# HD3SS460-PORT2.net
KiCad netlist of a schematic drawn in Altium Designer
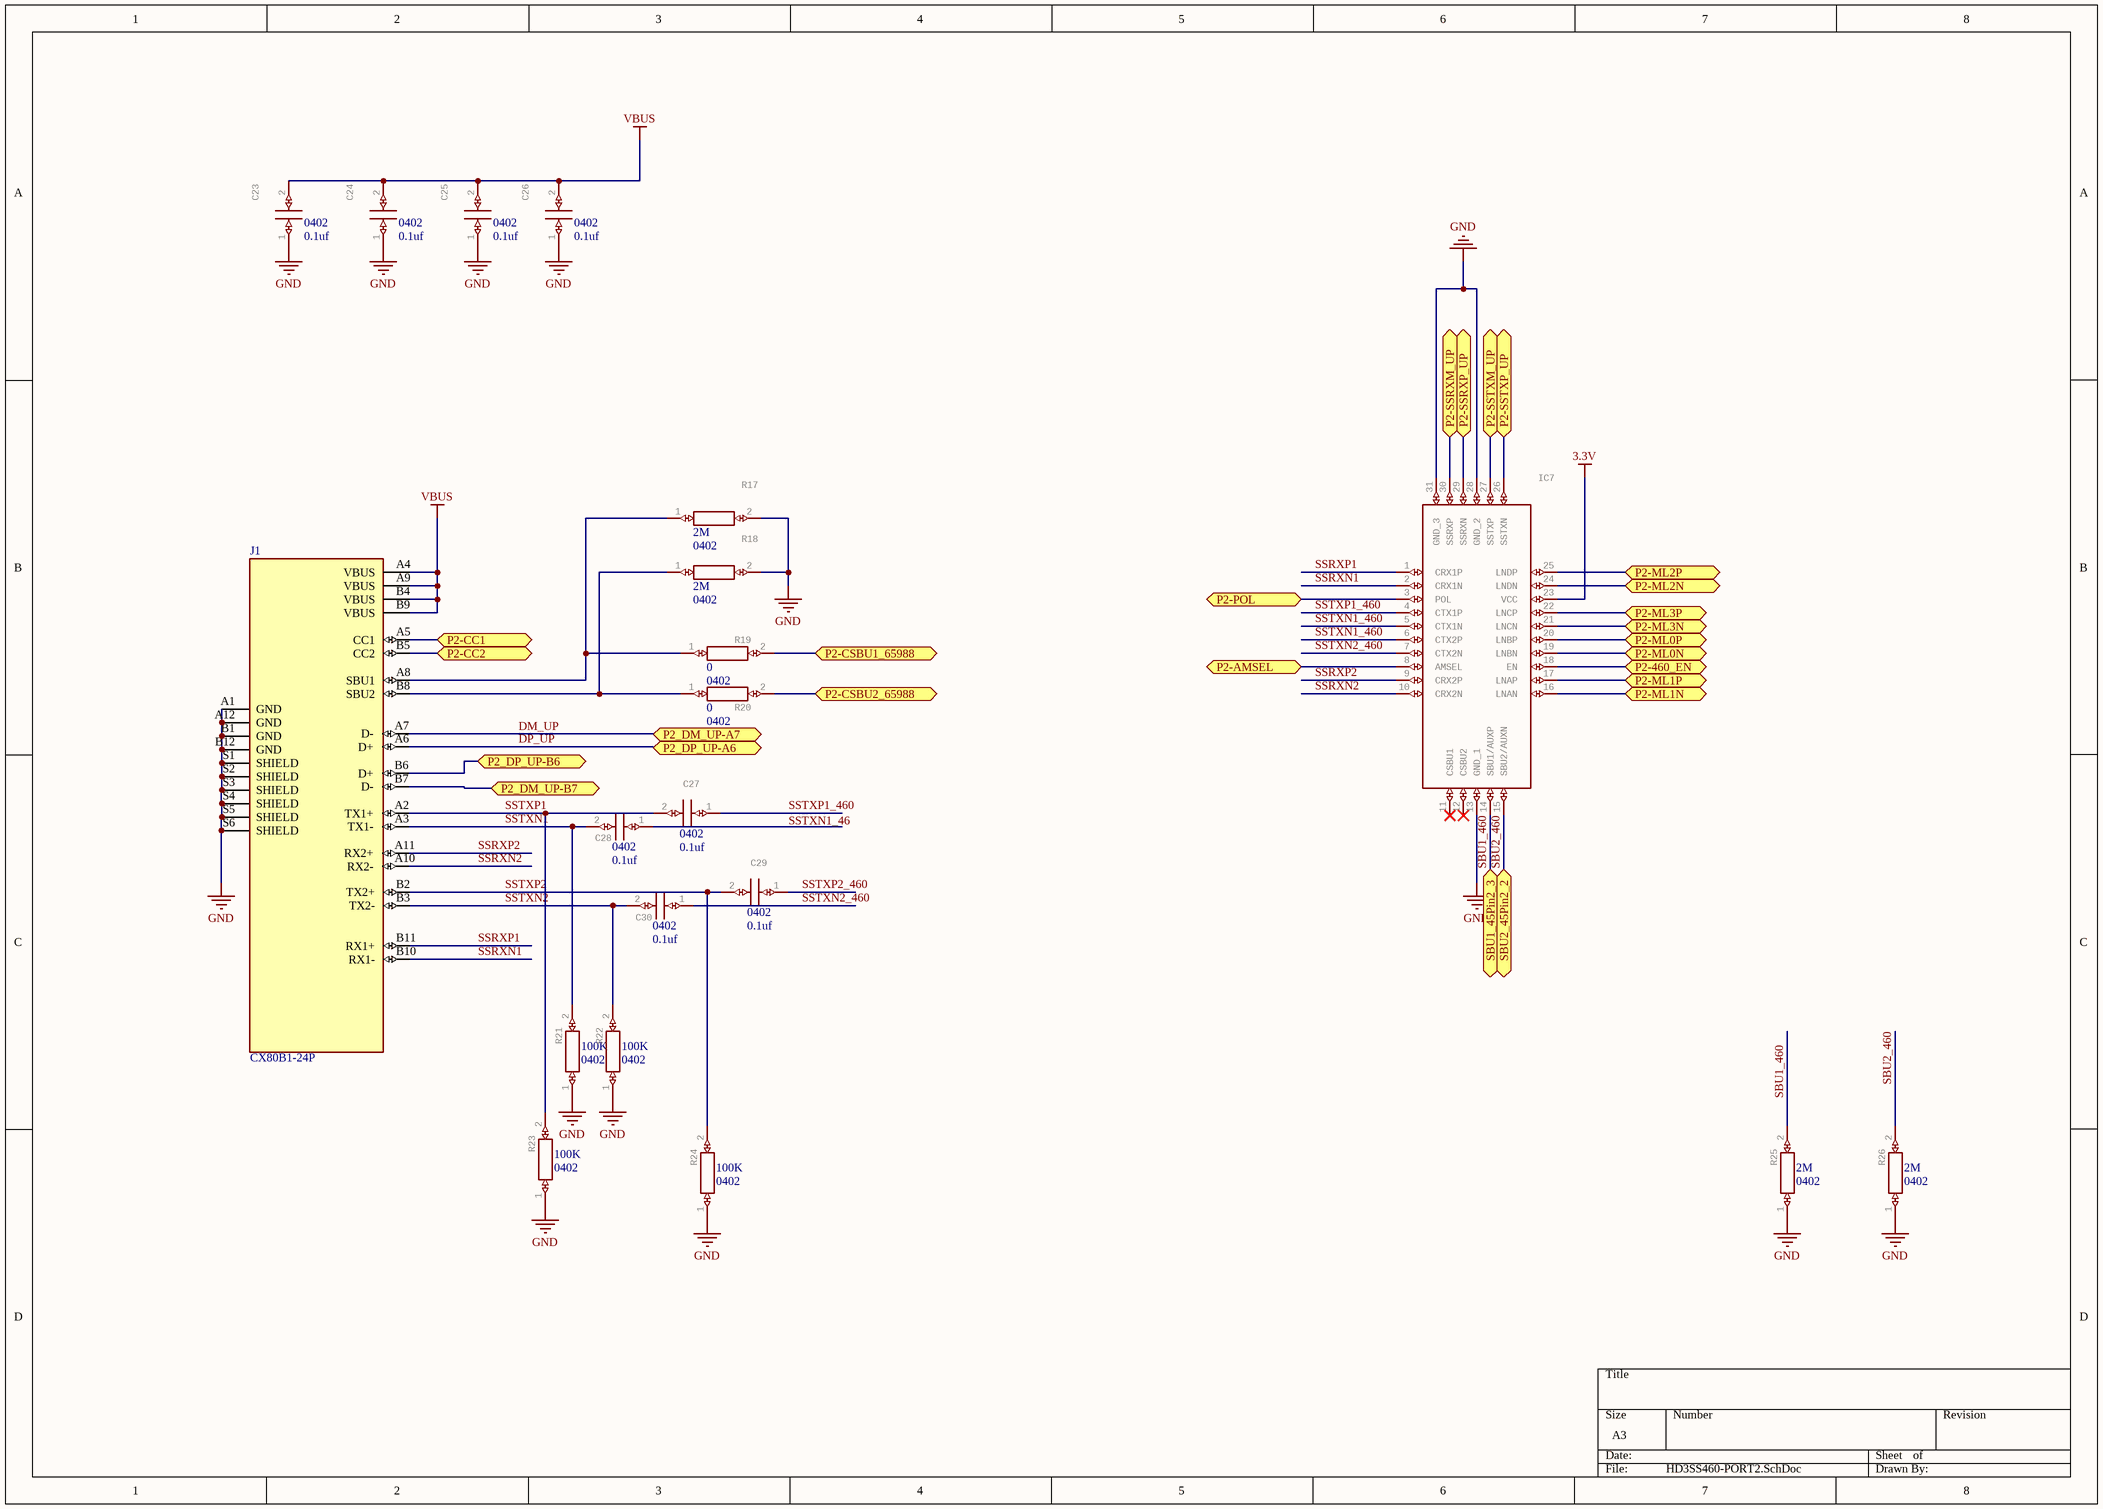
[diagram p0: HD3SS460-PORT2.SchDoc]

(export (version "E")
  (design (tool "Eeschema 10.0.6"))
  (components
    (comp (ref "C23")
      (value "0.1uf")
      (footprint "CAPC1005X56N")
      (fields
        (field (name "MANUFACTURER_PART_NUMBER") "04025C104KAT2A")
        (field (name "MOUSER_PART_NUMBER") "581-04025C104KAT2A")
        (field (name "PACKAGE") "0402")
        (field (name "Comment") "Multilayer Ceramic Capacitors MLCC - SMD/SMT 50V .1uF X7R 0402 10% Tol   Source:  Datasheet")
      )
      (libsource (lib "C0402-GP") (part "04025C104KAT2A"))
    )
    (comp (ref "C24")
      (value "0.1uf")
      (footprint "CAPC1005X56N")
      (fields
        (field (name "MANUFACTURER_PART_NUMBER") "04025C104KAT2A")
        (field (name "MOUSER_PART_NUMBER") "581-04025C104KAT2A")
        (field (name "PACKAGE") "0402")
        (field (name "Comment") "Multilayer Ceramic Capacitors MLCC - SMD/SMT 50V .1uF X7R 0402 10% Tol   Source:  Datasheet")
      )
      (libsource (lib "C0402-GP") (part "04025C104KAT2A"))
    )
    (comp (ref "C25")
      (value "0.1uf")
      (footprint "CAPC1005X56N")
      (fields
        (field (name "MANUFACTURER_PART_NUMBER") "04025C104KAT2A")
        (field (name "MOUSER_PART_NUMBER") "581-04025C104KAT2A")
        (field (name "PACKAGE") "0402")
        (field (name "Comment") "Multilayer Ceramic Capacitors MLCC - SMD/SMT 50V .1uF X7R 0402 10% Tol   Source:  Datasheet")
      )
      (libsource (lib "C0402-GP") (part "04025C104KAT2A"))
    )
    (comp (ref "C26")
      (value "0.1uf")
      (footprint "CAPC1005X56N")
      (fields
        (field (name "MANUFACTURER_PART_NUMBER") "04025C104KAT2A")
        (field (name "MOUSER_PART_NUMBER") "581-04025C104KAT2A")
        (field (name "PACKAGE") "0402")
        (field (name "Comment") "Multilayer Ceramic Capacitors MLCC - SMD/SMT 50V .1uF X7R 0402 10% Tol   Source:  Datasheet")
      )
      (libsource (lib "C0402-GP") (part "04025C104KAT2A"))
    )
    (comp (ref "C27")
      (value "0.1uf")
      (footprint "CAPC1005X56N")
      (fields
        (field (name "MANUFACTURER_PART_NUMBER") "04025C104KAT2A")
        (field (name "MOUSER_PART_NUMBER") "581-04025C104KAT2A")
        (field (name "PACKAGE") "0402")
        (field (name "Comment") "Multilayer Ceramic Capacitors MLCC - SMD/SMT 50V .1uF X7R 0402 10% Tol   Source:  Datasheet")
      )
      (libsource (lib "C0402-GP") (part "04025C104KAT2A"))
    )
    (comp (ref "C28")
      (value "0.1uf")
      (footprint "CAPC1005X56N")
      (fields
        (field (name "MANUFACTURER_PART_NUMBER") "04025C104KAT2A")
        (field (name "MOUSER_PART_NUMBER") "581-04025C104KAT2A")
        (field (name "PACKAGE") "0402")
        (field (name "Comment") "Multilayer Ceramic Capacitors MLCC - SMD/SMT 50V .1uF X7R 0402 10% Tol   Source:  Datasheet")
      )
      (libsource (lib "C0402-GP") (part "04025C104KAT2A"))
    )
    (comp (ref "C29")
      (value "0.1uf")
      (footprint "CAPC1005X56N")
      (fields
        (field (name "MANUFACTURER_PART_NUMBER") "04025C104KAT2A")
        (field (name "MOUSER_PART_NUMBER") "581-04025C104KAT2A")
        (field (name "PACKAGE") "0402")
        (field (name "Comment") "Multilayer Ceramic Capacitors MLCC - SMD/SMT 50V .1uF X7R 0402 10% Tol   Source:  Datasheet")
      )
      (libsource (lib "C0402-GP") (part "04025C104KAT2A"))
    )
    (comp (ref "C30")
      (value "0.1uf")
      (footprint "CAPC1005X56N")
      (fields
        (field (name "MANUFACTURER_PART_NUMBER") "04025C104KAT2A")
        (field (name "MOUSER_PART_NUMBER") "581-04025C104KAT2A")
        (field (name "PACKAGE") "0402")
        (field (name "Comment") "Multilayer Ceramic Capacitors MLCC - SMD/SMT 50V .1uF X7R 0402 10% Tol   Source:  Datasheet")
      )
      (libsource (lib "C0402-GP") (part "04025C104KAT2A"))
    )
    (comp (ref "IC7")
      (value "USB Type-C Alternate Mode 4x6 Differential Switch   Source:  Datasheet")
      (footprint "QFN40P250X450X80-31N")
      (fields
        (field (name "MANUFACTURER_PART_NUMBER") "HD3SS460RNHR")
        (field (name "MOUSER_PART_NUMBER") "595-HD3SS460RNHR")
      )
      (libsource (lib "HD3SS460RNHR") (part "HD3SS460RNHR"))
    )
    (comp (ref "J1")
      (value "CX80B1-24P")
      (footprint "HIROSE_CX80B1-24P")
      (fields
        (field (name "DIGI-KEY_PART_NUMBER") "26-CX80B1-24PCT-ND")
        (field (name "MF") "Hirose Electric Co Ltd")
      )
      (libsource (lib "CX80B1-24P") (part "CX80B1-24P"))
    )
    (comp (ref "R17")
      (value "2M")
      (footprint "RESC1005X40N")
      (fields
        (field (name "MANUFACTURER_PART_NUMBER") "RC0402FR-071KL")
        (field (name "MOUSER_PART_NUMBER") "603-RC0402FR-071KL")
        (field (name "PACKAGE") "0402")
        (field (name "Comment") "GENERAL PURPOSE CHIP RESISTORS   Source:  Datasheet")
      )
      (libsource (lib "R0402-GP") (part "RC0402FR-071KL"))
    )
    (comp (ref "R18")
      (value "2M")
      (footprint "RESC1005X40N")
      (fields
        (field (name "MANUFACTURER_PART_NUMBER") "RC0402FR-071KL")
        (field (name "MOUSER_PART_NUMBER") "603-RC0402FR-071KL")
        (field (name "PACKAGE") "0402")
        (field (name "Comment") "GENERAL PURPOSE CHIP RESISTORS   Source:  Datasheet")
      )
      (libsource (lib "R0402-GP") (part "RC0402FR-071KL"))
    )
    (comp (ref "R19")
      (value "0")
      (footprint "RESC1005X40N")
      (fields
        (field (name "MANUFACTURER_PART_NUMBER") "RC0402FR-071KL")
        (field (name "MOUSER_PART_NUMBER") "603-RC0402FR-071KL")
        (field (name "PACKAGE") "0402")
        (field (name "Comment") "GENERAL PURPOSE CHIP RESISTORS   Source:  Datasheet")
      )
      (libsource (lib "R0402-GP") (part "RC0402FR-071KL"))
    )
    (comp (ref "R20")
      (value "0")
      (footprint "RESC1005X40N")
      (fields
        (field (name "MANUFACTURER_PART_NUMBER") "RC0402FR-071KL")
        (field (name "MOUSER_PART_NUMBER") "603-RC0402FR-071KL")
        (field (name "PACKAGE") "0402")
        (field (name "Comment") "GENERAL PURPOSE CHIP RESISTORS   Source:  Datasheet")
      )
      (libsource (lib "R0402-GP") (part "RC0402FR-071KL"))
    )
    (comp (ref "R21")
      (value "100K")
      (footprint "RESC1005X40N")
      (fields
        (field (name "MANUFACTURER_PART_NUMBER") "RC0402FR-071KL")
        (field (name "MOUSER_PART_NUMBER") "603-RC0402FR-071KL")
        (field (name "PACKAGE") "0402")
        (field (name "Comment") "GENERAL PURPOSE CHIP RESISTORS   Source:  Datasheet")
      )
      (libsource (lib "R0402-GP") (part "RC0402FR-071KL"))
    )
    (comp (ref "R22")
      (value "100K")
      (footprint "RESC1005X40N")
      (fields
        (field (name "MANUFACTURER_PART_NUMBER") "RC0402FR-071KL")
        (field (name "MOUSER_PART_NUMBER") "603-RC0402FR-071KL")
        (field (name "PACKAGE") "0402")
        (field (name "Comment") "GENERAL PURPOSE CHIP RESISTORS   Source:  Datasheet")
      )
      (libsource (lib "R0402-GP") (part "RC0402FR-071KL"))
    )
    (comp (ref "R23")
      (value "100K")
      (footprint "RESC1005X40N")
      (fields
        (field (name "MANUFACTURER_PART_NUMBER") "RC0402FR-071KL")
        (field (name "MOUSER_PART_NUMBER") "603-RC0402FR-071KL")
        (field (name "PACKAGE") "0402")
        (field (name "Comment") "GENERAL PURPOSE CHIP RESISTORS   Source:  Datasheet")
      )
      (libsource (lib "R0402-GP") (part "RC0402FR-071KL"))
    )
    (comp (ref "R24")
      (value "100K")
      (footprint "RESC1005X40N")
      (fields
        (field (name "MANUFACTURER_PART_NUMBER") "RC0402FR-071KL")
        (field (name "MOUSER_PART_NUMBER") "603-RC0402FR-071KL")
        (field (name "PACKAGE") "0402")
        (field (name "Comment") "GENERAL PURPOSE CHIP RESISTORS   Source:  Datasheet")
      )
      (libsource (lib "R0402-GP") (part "RC0402FR-071KL"))
    )
    (comp (ref "R25")
      (value "2M")
      (footprint "RESC1005X40N")
      (fields
        (field (name "MANUFACTURER_PART_NUMBER") "RC0402FR-071KL")
        (field (name "MOUSER_PART_NUMBER") "603-RC0402FR-071KL")
        (field (name "PACKAGE") "0402")
        (field (name "Comment") "GENERAL PURPOSE CHIP RESISTORS   Source:  Datasheet")
      )
      (libsource (lib "R0402-GP") (part "RC0402FR-071KL"))
    )
    (comp (ref "R26")
      (value "2M")
      (footprint "RESC1005X40N")
      (fields
        (field (name "MANUFACTURER_PART_NUMBER") "RC0402FR-071KL")
        (field (name "MOUSER_PART_NUMBER") "603-RC0402FR-071KL")
        (field (name "PACKAGE") "0402")
        (field (name "Comment") "GENERAL PURPOSE CHIP RESISTORS   Source:  Datasheet")
      )
      (libsource (lib "R0402-GP") (part "RC0402FR-071KL"))
    )
  )
  (nets
    (net (code "2") (name "/DP_UP") (class "Default")
      (node (ref "J1") (pin "A6") (pinfunction "D+_A6") (pintype "bidirectional"))
    )
    (net (code "3") (name "/P2-460_EN") (class "Default")
      (node (ref "IC7") (pin "18") (pinfunction "EN_18") (pintype "bidirectional"))
    )
    (net (code "4") (name "/P2-AMSEL") (class "Default")
      (node (ref "IC7") (pin "8") (pinfunction "AMSEL_8") (pintype "bidirectional"))
    )
    (net (code "5") (name "/P2-CC1") (class "Default")
      (node (ref "J1") (pin "A5") (pinfunction "CC1_A5") (pintype "bidirectional"))
    )
    (net (code "6") (name "/P2-CC2") (class "Default")
      (node (ref "J1") (pin "B5") (pinfunction "CC2_B5") (pintype "bidirectional"))
    )
    (net (code "7") (name "/P2-CSBU1_65988") (class "Default")
      (node (ref "R19") (pin "2") (pinfunction "2_2") (pintype "bidirectional"))
    )
    (net (code "8") (name "/P2-CSBU2_65988") (class "Default")
      (node (ref "R20") (pin "2") (pinfunction "2_2") (pintype "bidirectional"))
    )
    (net (code "9") (name "/P2-ML0N") (class "Default")
      (node (ref "IC7") (pin "19") (pinfunction "LNBN_19") (pintype "bidirectional"))
    )
    (net (code "10") (name "/P2-ML0P") (class "Default")
      (node (ref "IC7") (pin "20") (pinfunction "LNBP_20") (pintype "bidirectional"))
    )
    (net (code "11") (name "/P2-ML1N") (class "Default")
      (node (ref "IC7") (pin "16") (pinfunction "LNAN_16") (pintype "bidirectional"))
    )
    (net (code "12") (name "/P2-ML1P") (class "Default")
      (node (ref "IC7") (pin "17") (pinfunction "LNAP_17") (pintype "bidirectional"))
    )
    (net (code "13") (name "/P2-ML2N") (class "Default")
      (node (ref "IC7") (pin "24") (pinfunction "LNDN_24") (pintype "bidirectional"))
    )
    (net (code "14") (name "/P2-ML2P") (class "Default")
      (node (ref "IC7") (pin "25") (pinfunction "LNDP_25") (pintype "bidirectional"))
    )
    (net (code "15") (name "/P2-ML3N") (class "Default")
      (node (ref "IC7") (pin "21") (pinfunction "LNCN_21") (pintype "bidirectional"))
    )
    (net (code "16") (name "/P2-ML3P") (class "Default")
      (node (ref "IC7") (pin "22") (pinfunction "LNCP_22") (pintype "bidirectional"))
    )
    (net (code "17") (name "/P2-POL") (class "Default")
      (node (ref "IC7") (pin "3") (pinfunction "POL_3") (pintype "bidirectional"))
    )
    (net (code "18") (name "/P2-SSRXM_UP") (class "Default")
      (node (ref "IC7") (pin "30") (pinfunction "SSRXP_30") (pintype "bidirectional"))
    )
    (net (code "19") (name "/P2-SSRXP_UP") (class "Default")
      (node (ref "IC7") (pin "29") (pinfunction "SSRXN_29") (pintype "bidirectional"))
    )
    (net (code "20") (name "/P2-SSTXM_UP") (class "Default")
      (node (ref "IC7") (pin "27") (pinfunction "SSTXP_27") (pintype "bidirectional"))
    )
    (net (code "21") (name "/P2-SSTXP_UP") (class "Default")
      (node (ref "IC7") (pin "26") (pinfunction "SSTXN_26") (pintype "bidirectional"))
    )
    (net (code "23") (name "/P2_DM_UP-B7") (class "Default")
      (node (ref "J1") (pin "B7") (pinfunction "D-_B7") (pintype "bidirectional"))
    )
    (net (code "25") (name "/P2_DP_UP-B6") (class "Default")
      (node (ref "J1") (pin "B6") (pinfunction "D+_B6") (pintype "bidirectional"))
    )
    (net (code "26") (name "/SBU1_460") (class "Default")
      (node (ref "IC7") (pin "14") (pinfunction "SBU1/AUXP_14") (pintype "bidirectional"))
      (node (ref "R25") (pin "2") (pinfunction "2_2") (pintype "bidirectional"))
    )
    (net (code "27") (name "/SBU2_460") (class "Default")
      (node (ref "IC7") (pin "15") (pinfunction "SBU2/AUXN_15") (pintype "bidirectional"))
      (node (ref "R26") (pin "2") (pinfunction "2_2") (pintype "bidirectional"))
    )
    (net (code "28") (name "/SSRXN1") (class "Default")
      (node (ref "IC7") (pin "2") (pinfunction "CRX1N_2") (pintype "bidirectional"))
      (node (ref "J1") (pin "B10") (pinfunction "RX1-_B10") (pintype "bidirectional"))
    )
    (net (code "29") (name "/SSRXN2") (class "Default")
      (node (ref "IC7") (pin "10") (pinfunction "CRX2N_10") (pintype "bidirectional"))
      (node (ref "J1") (pin "A10") (pinfunction "RX2-_A10") (pintype "bidirectional"))
    )
    (net (code "30") (name "/SSRXP1") (class "Default")
      (node (ref "IC7") (pin "1") (pinfunction "CRX1P_1") (pintype "bidirectional"))
      (node (ref "J1") (pin "B11") (pinfunction "RX1+_B11") (pintype "bidirectional"))
    )
    (net (code "31") (name "/SSRXP2") (class "Default")
      (node (ref "IC7") (pin "9") (pinfunction "CRX2P_9") (pintype "bidirectional"))
      (node (ref "J1") (pin "A11") (pinfunction "RX2+_A11") (pintype "bidirectional"))
    )
    (net (code "32") (name "/SSTXN1") (class "Default")
      (node (ref "C28") (pin "2") (pinfunction "2_2") (pintype "bidirectional"))
      (node (ref "J1") (pin "A3") (pinfunction "TX1-_A3") (pintype "bidirectional"))
      (node (ref "R21") (pin "2") (pinfunction "2_2") (pintype "bidirectional"))
    )
    (net (code "34") (name "/SSTXN1_460") (class "Default")
      (node (ref "IC7") (pin "5") (pinfunction "CTX1N_5") (pintype "bidirectional"))
      (node (ref "IC7") (pin "6") (pinfunction "CTX2P_6") (pintype "bidirectional"))
    )
    (net (code "35") (name "/SSTXN2") (class "Default")
      (node (ref "C30") (pin "2") (pinfunction "2_2") (pintype "bidirectional"))
      (node (ref "J1") (pin "B3") (pinfunction "TX2-_B3") (pintype "bidirectional"))
      (node (ref "R22") (pin "2") (pinfunction "2_2") (pintype "bidirectional"))
    )
    (net (code "36") (name "/SSTXN2_460") (class "Default")
      (node (ref "C30") (pin "1") (pinfunction "1_1") (pintype "bidirectional"))
      (node (ref "IC7") (pin "7") (pinfunction "CTX2N_7") (pintype "bidirectional"))
    )
    (net (code "37") (name "/SSTXP1") (class "Default")
      (node (ref "C27") (pin "2") (pinfunction "2_2") (pintype "bidirectional"))
      (node (ref "J1") (pin "A2") (pinfunction "TX1+_A2") (pintype "bidirectional"))
      (node (ref "R23") (pin "2") (pinfunction "2_2") (pintype "bidirectional"))
    )
    (net (code "38") (name "/SSTXP1_460") (class "Default")
      (node (ref "C27") (pin "1") (pinfunction "1_1") (pintype "bidirectional"))
      (node (ref "IC7") (pin "4") (pinfunction "CTX1P_4") (pintype "bidirectional"))
    )
    (net (code "39") (name "/SSTXP2") (class "Default")
      (node (ref "C29") (pin "2") (pinfunction "2_2") (pintype "bidirectional"))
      (node (ref "J1") (pin "B2") (pinfunction "TX2+_B2") (pintype "bidirectional"))
      (node (ref "R24") (pin "2") (pinfunction "2_2") (pintype "bidirectional"))
    )
    (net (code "40") (name "/SSTXP2_460") (class "Default")
      (node (ref "C29") (pin "1") (pinfunction "1_1") (pintype "bidirectional"))
    )
    (net (code "41") (name "3.3V") (class "Default")
      (node (ref "IC7") (pin "23") (pinfunction "VCC_23") (pintype "bidirectional"))
    )
    (net (code "42") (name "GND") (class "Default")
      (node (ref "C23") (pin "1") (pinfunction "1_1") (pintype "bidirectional"))
      (node (ref "C24") (pin "1") (pinfunction "1_1") (pintype "bidirectional"))
      (node (ref "C25") (pin "1") (pinfunction "1_1") (pintype "bidirectional"))
      (node (ref "C26") (pin "1") (pinfunction "1_1") (pintype "bidirectional"))
      (node (ref "IC7") (pin "13") (pinfunction "GND_1_13") (pintype "bidirectional"))
      (node (ref "IC7") (pin "28") (pinfunction "GND_2_28") (pintype "bidirectional"))
      (node (ref "IC7") (pin "31") (pinfunction "GND_3_31") (pintype "bidirectional"))
      (node (ref "J1") (pin "A1") (pinfunction "GND_A1") (pintype "power_in"))
      (node (ref "J1") (pin "A12") (pinfunction "GND_A12") (pintype "power_in"))
      (node (ref "J1") (pin "B1") (pinfunction "GND_B1") (pintype "power_in"))
      (node (ref "J1") (pin "B12") (pinfunction "GND_B12") (pintype "power_in"))
      (node (ref "J1") (pin "S1") (pinfunction "SHIELD_S1") (pintype "power_in"))
      (node (ref "J1") (pin "S2") (pinfunction "SHIELD_S2") (pintype "power_in"))
      (node (ref "J1") (pin "S3") (pinfunction "SHIELD_S3") (pintype "power_in"))
      (node (ref "J1") (pin "S4") (pinfunction "SHIELD_S4") (pintype "power_in"))
      (node (ref "J1") (pin "S5") (pinfunction "SHIELD_S5") (pintype "power_in"))
      (node (ref "J1") (pin "S6") (pinfunction "SHIELD_S6") (pintype "power_in"))
      (node (ref "R17") (pin "2") (pinfunction "2_2") (pintype "bidirectional"))
      (node (ref "R18") (pin "2") (pinfunction "2_2") (pintype "bidirectional"))
      (node (ref "R21") (pin "1") (pinfunction "1_1") (pintype "bidirectional"))
      (node (ref "R22") (pin "1") (pinfunction "1_1") (pintype "bidirectional"))
      (node (ref "R23") (pin "1") (pinfunction "1_1") (pintype "bidirectional"))
      (node (ref "R24") (pin "1") (pinfunction "1_1") (pintype "bidirectional"))
      (node (ref "R25") (pin "1") (pinfunction "1_1") (pintype "bidirectional"))
      (node (ref "R26") (pin "1") (pinfunction "1_1") (pintype "bidirectional"))
    )
    (net (code "43") (name "Net-(J1-SBU1)") (class "Default")
      (node (ref "J1") (pin "A8") (pinfunction "SBU1_A8") (pintype "bidirectional"))
      (node (ref "R17") (pin "1") (pinfunction "1_1") (pintype "bidirectional"))
      (node (ref "R19") (pin "1") (pinfunction "1_1") (pintype "bidirectional"))
    )
    (net (code "44") (name "Net-(J1-SBU2)") (class "Default")
      (node (ref "J1") (pin "B8") (pinfunction "SBU2_B8") (pintype "bidirectional"))
      (node (ref "R18") (pin "1") (pinfunction "1_1") (pintype "bidirectional"))
      (node (ref "R20") (pin "1") (pinfunction "1_1") (pintype "bidirectional"))
    )
    (net (code "45") (name "VBUS") (class "Default")
      (node (ref "C23") (pin "2") (pinfunction "2_2") (pintype "bidirectional"))
      (node (ref "C24") (pin "2") (pinfunction "2_2") (pintype "bidirectional"))
      (node (ref "C25") (pin "2") (pinfunction "2_2") (pintype "bidirectional"))
      (node (ref "C26") (pin "2") (pinfunction "2_2") (pintype "bidirectional"))
      (node (ref "J1") (pin "A4") (pinfunction "VBUS_A4") (pintype "power_in"))
      (node (ref "J1") (pin "A9") (pinfunction "VBUS_A9") (pintype "power_in"))
      (node (ref "J1") (pin "B4") (pinfunction "VBUS_B4") (pintype "power_in"))
      (node (ref "J1") (pin "B9") (pinfunction "VBUS_B9") (pintype "power_in"))
    )
    (net (code "46") (name "unconnected-(C28-Pad1)") (class "Default")
      (node (ref "C28") (pin "1") (pinfunction "1_1") (pintype "bidirectional"))
    )
    (net (code "47") (name "unconnected-(IC7-CSBU1-Pad11)") (class "Default")
      (node (ref "IC7") (pin "11") (pinfunction "CSBU1_11") (pintype "bidirectional+no_connect"))
    )
    (net (code "48") (name "unconnected-(IC7-CSBU2-Pad12)") (class "Default")
      (node (ref "IC7") (pin "12") (pinfunction "CSBU2_12") (pintype "bidirectional+no_connect"))
    )
    (net (code "49") (name "unconnected-(J1-D--PadA7)") (class "Default")
      (node (ref "J1") (pin "A7") (pinfunction "D-_A7") (pintype "bidirectional"))
    )
  )
)
